# SH3_-_5V_POWER.net
KiCad netlist of a schematic drawn in Altium Designer
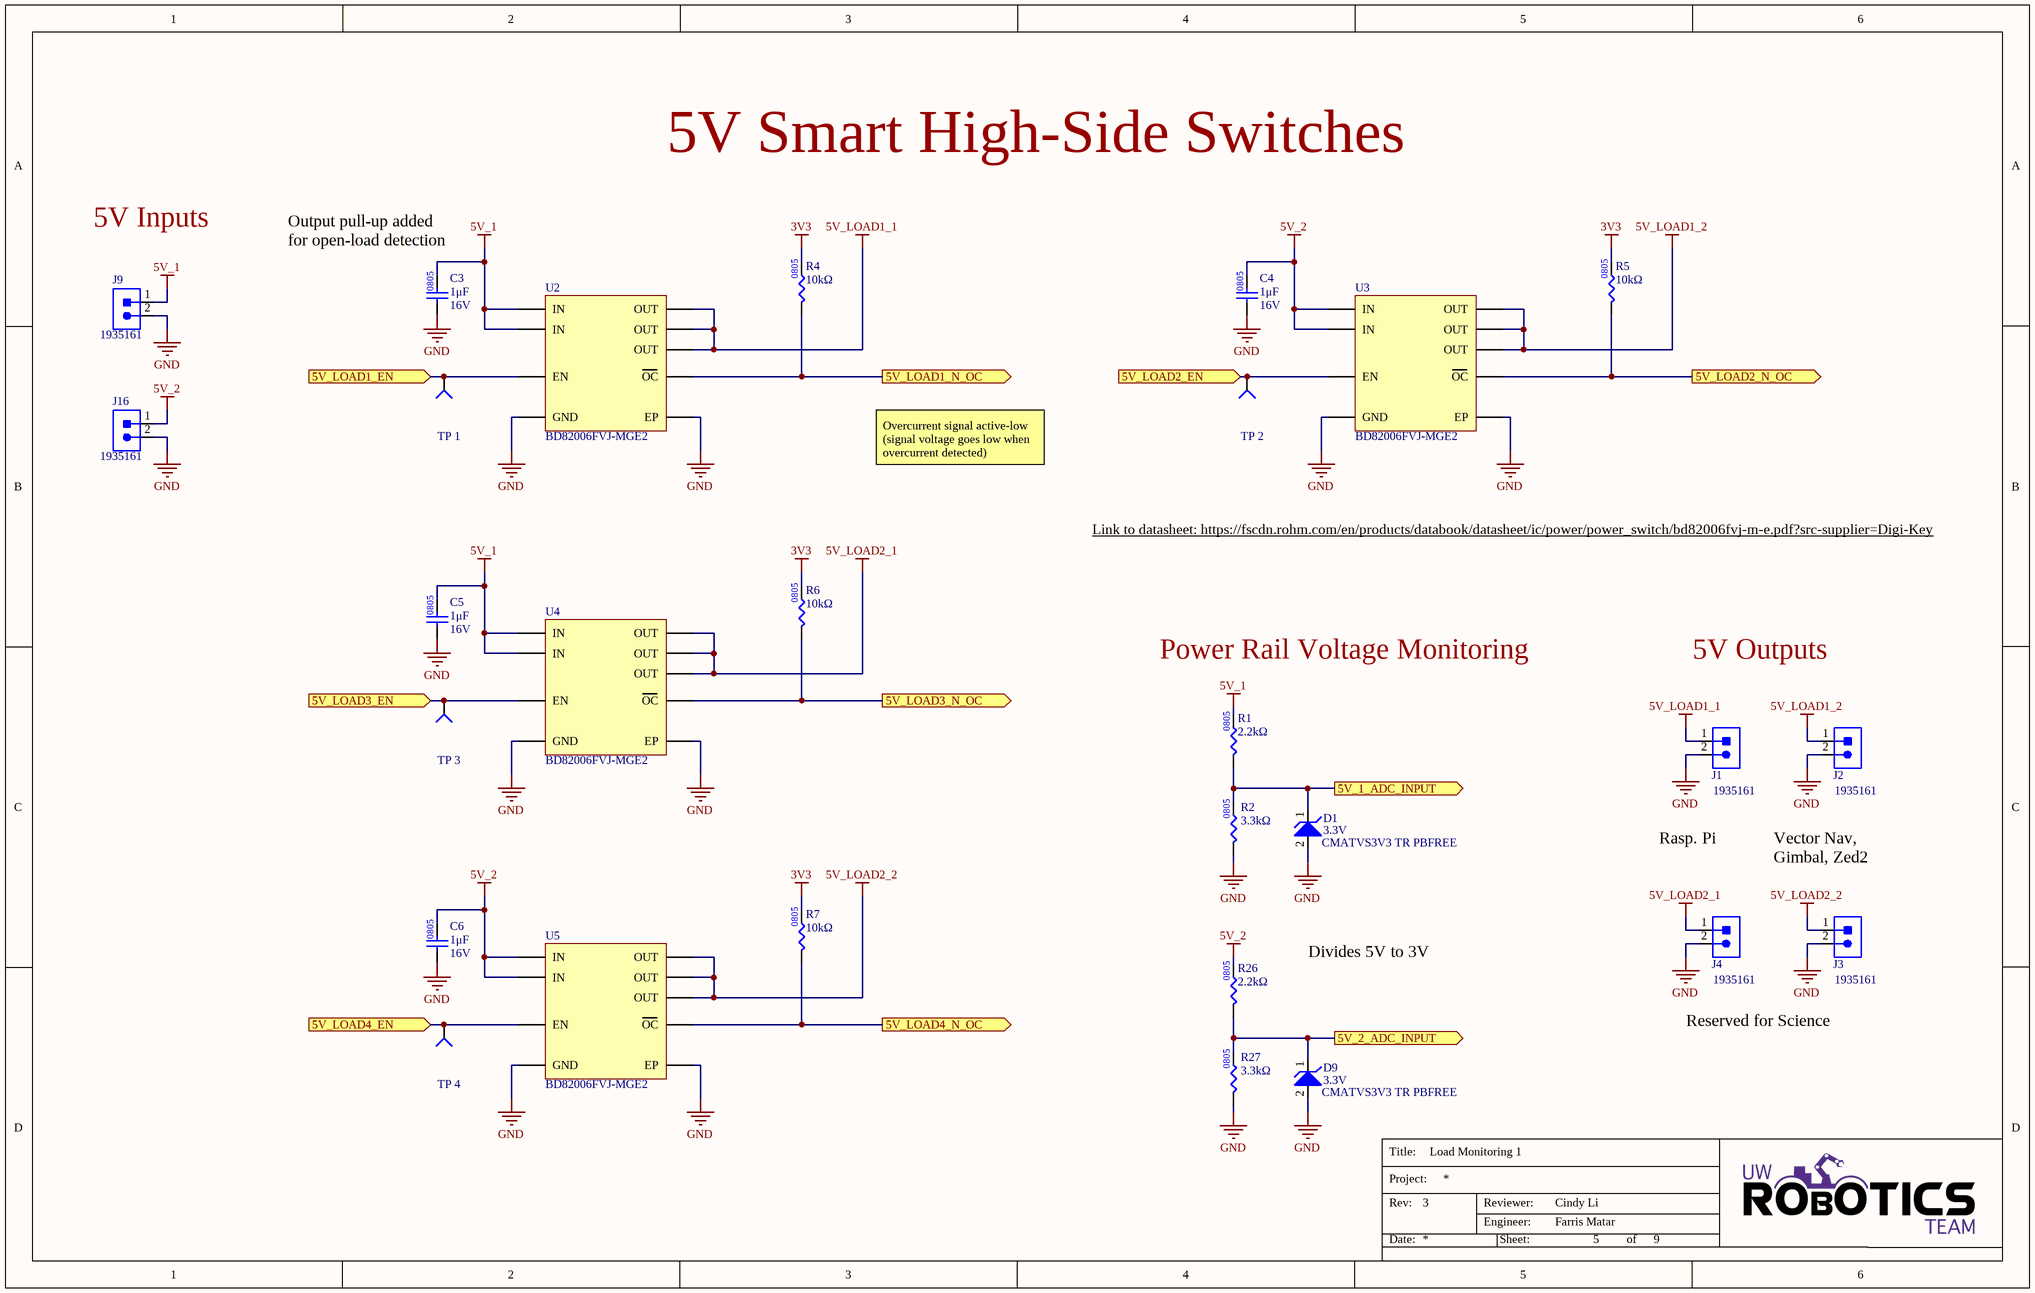
[diagram p0: SH3 - 5V POWER.SchDoc]

(export (version "E")
  (design (tool "Eeschema 10.0.6"))
  (components
    (comp (ref "C3")
      (value "1μF")
      (footprint "CAP0805")
      (description "CAP CER 1UF 16V X7R 0805")
      (fields (field (name "VOLTAGE RATING") "16V") (field (name "Comment") "CAP_1uF_16V_0805"))
      (libsource (lib "UWRT_Schematic_Library_2020") (part "CAP_1uF_16V_0805"))
    )
    (comp (ref "C4")
      (value "1μF")
      (footprint "CAP0805")
      (description "CAP CER 1UF 16V X7R 0805")
      (fields (field (name "VOLTAGE RATING") "16V") (field (name "Comment") "CAP_1uF_16V_0805"))
      (libsource (lib "UWRT_Schematic_Library_2020") (part "CAP_1uF_16V_0805"))
    )
    (comp (ref "C5")
      (value "1μF")
      (footprint "CAP0805")
      (description "CAP CER 1UF 16V X7R 0805")
      (fields (field (name "VOLTAGE RATING") "16V") (field (name "Comment") "CAP_1uF_16V_0805"))
      (libsource (lib "UWRT_Schematic_Library_2020") (part "CAP_1uF_16V_0805"))
    )
    (comp (ref "C6")
      (value "1μF")
      (footprint "CAP0805")
      (description "CAP CER 1UF 16V X7R 0805")
      (fields (field (name "VOLTAGE RATING") "16V") (field (name "Comment") "CAP_1uF_16V_0805"))
      (libsource (lib "UWRT_Schematic_Library_2020") (part "CAP_1uF_16V_0805"))
    )
    (comp (ref "D1")
      (value "TVS_DIODE_UNIDIR_3.3V_7A")
      (footprint "SOD-923")
      (description "TVS DIODE 3.3VWM 11VC SOD923")
      (fields
        (field (name "MANUFACTURER PART NUMBER 1") "CMATVS3V3 TR PBFREE")
        (field (name "VOLTAGE - REVERSE STANDOFF (TYP)") "3.3V")
      )
      (libsource (lib "UWRT_Schematic_Library_2020") (part "TVS_DIODE_UNIDIR_3.3V_7A"))
    )
    (comp (ref "D9")
      (value "TVS_DIODE_UNIDIR_3.3V_7A")
      (footprint "SOD-923")
      (description "TVS DIODE 3.3VWM 11VC SOD923")
      (fields
        (field (name "MANUFACTURER PART NUMBER 1") "CMATVS3V3 TR PBFREE")
        (field (name "VOLTAGE - REVERSE STANDOFF (TYP)") "3.3V")
      )
      (libsource (lib "UWRT_Schematic_Library_2020") (part "TVS_DIODE_UNIDIR_3.3V_7A"))
    )
    (comp (ref "J1")
      (value "CON_2M_TERM")
      (footprint "1935161")
      (description "TERM BLK 2POS SIDE ENTRY 5MM")
      (fields (field (name "VOLTAGE") "300V") (field (name "MANUFACTURER PART NUMBER 1") "1935161"))
      (libsource (lib "UWRT_Schematic_Library_2020") (part "CON_2M_TERM"))
    )
    (comp (ref "J2")
      (value "CON_2M_TERM")
      (footprint "1935161")
      (description "TERM BLK 2POS SIDE ENTRY 5MM")
      (fields (field (name "VOLTAGE") "300V") (field (name "MANUFACTURER PART NUMBER 1") "1935161"))
      (libsource (lib "UWRT_Schematic_Library_2020") (part "CON_2M_TERM"))
    )
    (comp (ref "J3")
      (value "CON_2M_TERM")
      (footprint "1935161")
      (description "TERM BLK 2POS SIDE ENTRY 5MM")
      (fields (field (name "VOLTAGE") "300V") (field (name "MANUFACTURER PART NUMBER 1") "1935161"))
      (libsource (lib "UWRT_Schematic_Library_2020") (part "CON_2M_TERM"))
    )
    (comp (ref "J4")
      (value "CON_2M_TERM")
      (footprint "1935161")
      (description "TERM BLK 2POS SIDE ENTRY 5MM")
      (fields (field (name "VOLTAGE") "300V") (field (name "MANUFACTURER PART NUMBER 1") "1935161"))
      (libsource (lib "UWRT_Schematic_Library_2020") (part "CON_2M_TERM"))
    )
    (comp (ref "J9")
      (value "CON_2M_TERM")
      (footprint "1935161")
      (description "TERM BLK 2POS SIDE ENTRY 5MM")
      (fields (field (name "VOLTAGE") "300V") (field (name "MANUFACTURER PART NUMBER 1") "1935161"))
      (libsource (lib "") (part "CON_2M_TERM_1"))
    )
    (comp (ref "J16")
      (value "CON_2M_TERM")
      (footprint "1935161")
      (description "TERM BLK 2POS SIDE ENTRY 5MM")
      (fields (field (name "VOLTAGE") "300V") (field (name "MANUFACTURER PART NUMBER 1") "1935161"))
      (libsource (lib "") (part "CON_2M_TERM_1"))
    )
    (comp (ref "R1")
      (value "2.2kΩ")
      (footprint "RES0805")
      (description "RES 2.2K OHM 5% 1/8W 0805")
      (fields (field (name "TOLERANCE") "5%") (field (name "Comment") "RES_2.2kΩ_0805"))
      (libsource (lib "UWRT_Schematic_Library_2020") (part "RES_2.2kΩ_0805_5%"))
    )
    (comp (ref "R2")
      (value "3.3kΩ")
      (footprint "RES0805")
      (description "RES 3.3K OHM 1% 1/8W 0805")
      (fields (field (name "LCSC PART #") "C26010") (field (name "Comment") "RES_3.3kΩ_0805_1%"))
      (libsource (lib "UWRT_Schematic_Library_2020") (part "RES_3.3kΩ_0805_1%"))
    )
    (comp (ref "R4")
      (value "10kΩ")
      (footprint "RES0805")
      (description "RES 10K OHM 5% 1/8W 0805")
      (fields (field (name "LCSC PART #") "C17414") (field (name "Comment") "RES_10kΩ_0805_5%"))
      (libsource (lib "UWRT_Schematic_Library_2020") (part "RES_10kΩ_0805_5%"))
    )
    (comp (ref "R5")
      (value "10kΩ")
      (footprint "RES0805")
      (description "RES 10K OHM 5% 1/8W 0805")
      (fields (field (name "LCSC PART #") "C17414") (field (name "Comment") "RES_10kΩ_0805_5%"))
      (libsource (lib "UWRT_Schematic_Library_2020") (part "RES_10kΩ_0805_5%"))
    )
    (comp (ref "R6")
      (value "10kΩ")
      (footprint "RES0805")
      (description "RES 10K OHM 5% 1/8W 0805")
      (fields (field (name "LCSC PART #") "C17414") (field (name "Comment") "RES_10kΩ_0805_5%"))
      (libsource (lib "UWRT_Schematic_Library_2020") (part "RES_10kΩ_0805_5%"))
    )
    (comp (ref "R7")
      (value "10kΩ")
      (footprint "RES0805")
      (description "RES 10K OHM 5% 1/8W 0805")
      (fields (field (name "LCSC PART #") "C17414") (field (name "Comment") "RES_10kΩ_0805_5%"))
      (libsource (lib "UWRT_Schematic_Library_2020") (part "RES_10kΩ_0805_5%"))
    )
    (comp (ref "R26")
      (value "2.2kΩ")
      (footprint "RES0805")
      (description "RES 2.2K OHM 5% 1/8W 0805")
      (fields (field (name "TOLERANCE") "5%") (field (name "Comment") "RES_2.2kΩ_0805"))
      (libsource (lib "UWRT_Schematic_Library_2020") (part "RES_2.2kΩ_0805_5%"))
    )
    (comp (ref "R27")
      (value "3.3kΩ")
      (footprint "RES0805")
      (description "RES 3.3K OHM 1% 1/8W 0805")
      (fields (field (name "LCSC PART #") "C26010") (field (name "Comment") "RES_3.3kΩ_0805_1%"))
      (libsource (lib "UWRT_Schematic_Library_2020") (part "RES_3.3kΩ_0805_1%"))
    )
    (comp (ref "TP 1")
      (value "TESTPOINT_1MM_CIRCLE")
      (footprint "TESTPOINT_CIRCLE_1MM")
      (description "TESTPOINT 1MM CIRCLE")
      (libsource (lib "UWRT_Schematic_Library_2020") (part "TESTPOINT_1MM_CIRCLE"))
    )
    (comp (ref "TP 2")
      (value "TESTPOINT_1MM_CIRCLE")
      (footprint "TESTPOINT_CIRCLE_1MM")
      (description "TESTPOINT 1MM CIRCLE")
      (libsource (lib "UWRT_Schematic_Library_2020") (part "TESTPOINT_1MM_CIRCLE"))
    )
    (comp (ref "TP 3")
      (value "TESTPOINT_1MM_CIRCLE")
      (footprint "TESTPOINT_CIRCLE_1MM")
      (description "TESTPOINT 1MM CIRCLE")
      (libsource (lib "UWRT_Schematic_Library_2020") (part "TESTPOINT_1MM_CIRCLE"))
    )
    (comp (ref "TP 4")
      (value "TESTPOINT_1MM_CIRCLE")
      (footprint "TESTPOINT_CIRCLE_1MM")
      (description "TESTPOINT 1MM CIRCLE")
      (libsource (lib "UWRT_Schematic_Library_2020") (part "TESTPOINT_1MM_CIRCLE"))
    )
    (comp (ref "U2")
      (value "BD82006FVJ-MGE2")
      (footprint "8-TSSOP-BJ")
      (description "IC PWR SWITCH N-CHAN 1:1 8TSSOP")
      (fields (field (name "MANUFACTURER PART NUMBER 1") "BD82006FVJ-MGE2"))
      (libsource (lib "UWRT_Schematic_Library_2020") (part "BD82006FVJ-MGE2"))
    )
    (comp (ref "U3")
      (value "BD82006FVJ-MGE2")
      (footprint "8-TSSOP-BJ")
      (description "IC PWR SWITCH N-CHAN 1:1 8TSSOP")
      (fields (field (name "MANUFACTURER PART NUMBER 1") "BD82006FVJ-MGE2"))
      (libsource (lib "UWRT_Schematic_Library_2020") (part "BD82006FVJ-MGE2"))
    )
    (comp (ref "U4")
      (value "BD82006FVJ-MGE2")
      (footprint "8-TSSOP-BJ")
      (description "IC PWR SWITCH N-CHAN 1:1 8TSSOP")
      (fields (field (name "MANUFACTURER PART NUMBER 1") "BD82006FVJ-MGE2"))
      (libsource (lib "UWRT_Schematic_Library_2020") (part "BD82006FVJ-MGE2"))
    )
    (comp (ref "U5")
      (value "BD82006FVJ-MGE2")
      (footprint "8-TSSOP-BJ")
      (description "IC PWR SWITCH N-CHAN 1:1 8TSSOP")
      (fields (field (name "MANUFACTURER PART NUMBER 1") "BD82006FVJ-MGE2"))
      (libsource (lib "UWRT_Schematic_Library_2020") (part "BD82006FVJ-MGE2"))
    )
  )
  (nets
    (net (code "1") (name "/5V_1_ADC_INPUT") (class "Default")
      (node (ref "D1") (pin "1") (pinfunction "1_1") (pintype "passive"))
      (node (ref "R1") (pin "1") (pinfunction "1_1") (pintype "passive"))
      (node (ref "R2") (pin "2") (pinfunction "2_2") (pintype "passive"))
    )
    (net (code "2") (name "/5V_2_ADC_INPUT") (class "Default")
      (node (ref "D9") (pin "1") (pinfunction "1_1") (pintype "passive"))
      (node (ref "R26") (pin "1") (pinfunction "1_1") (pintype "passive"))
      (node (ref "R27") (pin "2") (pinfunction "2_2") (pintype "passive"))
    )
    (net (code "3") (name "/5V_LOAD1_EN") (class "Default")
      (node (ref "TP 1") (pin "1") (pinfunction "=value_1") (pintype "passive"))
      (node (ref "U2") (pin "4") (pinfunction "EN_4") (pintype "passive"))
    )
    (net (code "4") (name "/5V_LOAD1_N_OC") (class "Default")
      (node (ref "R4") (pin "1") (pinfunction "1_1") (pintype "passive"))
      (node (ref "U2") (pin "8") (pinfunction "OC_8") (pintype "passive"))
    )
    (net (code "5") (name "/5V_LOAD2_EN") (class "Default")
      (node (ref "TP 2") (pin "1") (pinfunction "=value_1") (pintype "passive"))
      (node (ref "U3") (pin "4") (pinfunction "EN_4") (pintype "passive"))
    )
    (net (code "6") (name "/5V_LOAD2_N_OC") (class "Default")
      (node (ref "R5") (pin "1") (pinfunction "1_1") (pintype "passive"))
      (node (ref "U3") (pin "8") (pinfunction "OC_8") (pintype "passive"))
    )
    (net (code "7") (name "/5V_LOAD3_EN") (class "Default")
      (node (ref "TP 3") (pin "1") (pinfunction "=value_1") (pintype "passive"))
      (node (ref "U4") (pin "4") (pinfunction "EN_4") (pintype "passive"))
    )
    (net (code "8") (name "/5V_LOAD3_N_OC") (class "Default")
      (node (ref "R6") (pin "1") (pinfunction "1_1") (pintype "passive"))
      (node (ref "U4") (pin "8") (pinfunction "OC_8") (pintype "passive"))
    )
    (net (code "9") (name "/5V_LOAD4_EN") (class "Default")
      (node (ref "TP 4") (pin "1") (pinfunction "=value_1") (pintype "passive"))
      (node (ref "U5") (pin "4") (pinfunction "EN_4") (pintype "passive"))
    )
    (net (code "10") (name "/5V_LOAD4_N_OC") (class "Default")
      (node (ref "R7") (pin "1") (pinfunction "1_1") (pintype "passive"))
      (node (ref "U5") (pin "8") (pinfunction "OC_8") (pintype "passive"))
    )
    (net (code "11") (name "3V3") (class "Default")
      (node (ref "R4") (pin "2") (pinfunction "2_2") (pintype "passive"))
      (node (ref "R5") (pin "2") (pinfunction "2_2") (pintype "passive"))
      (node (ref "R6") (pin "2") (pinfunction "2_2") (pintype "passive"))
      (node (ref "R7") (pin "2") (pinfunction "2_2") (pintype "passive"))
    )
    (net (code "12") (name "5V_1") (class "Default")
      (node (ref "C3") (pin "2") (pinfunction "2_2") (pintype "passive"))
      (node (ref "C5") (pin "2") (pinfunction "2_2") (pintype "passive"))
      (node (ref "J9") (pin "1") (pinfunction "1_1") (pintype "passive"))
      (node (ref "R1") (pin "2") (pinfunction "2_2") (pintype "passive"))
      (node (ref "U2") (pin "2") (pinfunction "IN_2") (pintype "passive"))
      (node (ref "U2") (pin "3") (pinfunction "IN_3") (pintype "passive"))
      (node (ref "U4") (pin "2") (pinfunction "IN_2") (pintype "passive"))
      (node (ref "U4") (pin "3") (pinfunction "IN_3") (pintype "passive"))
    )
    (net (code "13") (name "5V_2") (class "Default")
      (node (ref "C4") (pin "2") (pinfunction "2_2") (pintype "passive"))
      (node (ref "C6") (pin "2") (pinfunction "2_2") (pintype "passive"))
      (node (ref "J16") (pin "1") (pinfunction "1_1") (pintype "passive"))
      (node (ref "R26") (pin "2") (pinfunction "2_2") (pintype "passive"))
      (node (ref "U3") (pin "2") (pinfunction "IN_2") (pintype "passive"))
      (node (ref "U3") (pin "3") (pinfunction "IN_3") (pintype "passive"))
      (node (ref "U5") (pin "2") (pinfunction "IN_2") (pintype "passive"))
      (node (ref "U5") (pin "3") (pinfunction "IN_3") (pintype "passive"))
    )
    (net (code "14") (name "5V_LOAD1_1") (class "Default")
      (node (ref "J1") (pin "1") (pinfunction "1_1") (pintype "passive"))
      (node (ref "U2") (pin "5") (pinfunction "OUT_5") (pintype "passive"))
      (node (ref "U2") (pin "6") (pinfunction "OUT_6") (pintype "passive"))
      (node (ref "U2") (pin "7") (pinfunction "OUT_7") (pintype "passive"))
    )
    (net (code "15") (name "5V_LOAD1_2") (class "Default")
      (node (ref "J2") (pin "1") (pinfunction "1_1") (pintype "passive"))
      (node (ref "U3") (pin "5") (pinfunction "OUT_5") (pintype "passive"))
      (node (ref "U3") (pin "6") (pinfunction "OUT_6") (pintype "passive"))
      (node (ref "U3") (pin "7") (pinfunction "OUT_7") (pintype "passive"))
    )
    (net (code "16") (name "5V_LOAD2_1") (class "Default")
      (node (ref "J4") (pin "1") (pinfunction "1_1") (pintype "passive"))
      (node (ref "U4") (pin "5") (pinfunction "OUT_5") (pintype "passive"))
      (node (ref "U4") (pin "6") (pinfunction "OUT_6") (pintype "passive"))
      (node (ref "U4") (pin "7") (pinfunction "OUT_7") (pintype "passive"))
    )
    (net (code "17") (name "5V_LOAD2_2") (class "Default")
      (node (ref "J3") (pin "1") (pinfunction "1_1") (pintype "passive"))
      (node (ref "U5") (pin "5") (pinfunction "OUT_5") (pintype "passive"))
      (node (ref "U5") (pin "6") (pinfunction "OUT_6") (pintype "passive"))
      (node (ref "U5") (pin "7") (pinfunction "OUT_7") (pintype "passive"))
    )
    (net (code "18") (name "GND") (class "Default")
      (node (ref "C3") (pin "1") (pinfunction "1_1") (pintype "passive"))
      (node (ref "C4") (pin "1") (pinfunction "1_1") (pintype "passive"))
      (node (ref "C5") (pin "1") (pinfunction "1_1") (pintype "passive"))
      (node (ref "C6") (pin "1") (pinfunction "1_1") (pintype "passive"))
      (node (ref "D1") (pin "2") (pinfunction "2_2") (pintype "passive"))
      (node (ref "D9") (pin "2") (pinfunction "2_2") (pintype "passive"))
      (node (ref "J1") (pin "2") (pinfunction "2_2") (pintype "passive"))
      (node (ref "J16") (pin "2") (pinfunction "2_2") (pintype "passive"))
      (node (ref "J2") (pin "2") (pinfunction "2_2") (pintype "passive"))
      (node (ref "J3") (pin "2") (pinfunction "2_2") (pintype "passive"))
      (node (ref "J4") (pin "2") (pinfunction "2_2") (pintype "passive"))
      (node (ref "J9") (pin "2") (pinfunction "2_2") (pintype "passive"))
      (node (ref "R2") (pin "1") (pinfunction "1_1") (pintype "passive"))
      (node (ref "R27") (pin "1") (pinfunction "1_1") (pintype "passive"))
      (node (ref "U2") (pin "1") (pinfunction "GND_1") (pintype "passive"))
      (node (ref "U2") (pin "9") (pinfunction "EP_9") (pintype "passive"))
      (node (ref "U3") (pin "1") (pinfunction "GND_1") (pintype "passive"))
      (node (ref "U3") (pin "9") (pinfunction "EP_9") (pintype "passive"))
      (node (ref "U4") (pin "1") (pinfunction "GND_1") (pintype "passive"))
      (node (ref "U4") (pin "9") (pinfunction "EP_9") (pintype "passive"))
      (node (ref "U5") (pin "1") (pinfunction "GND_1") (pintype "passive"))
      (node (ref "U5") (pin "9") (pinfunction "EP_9") (pintype "passive"))
    )
  )
)
